# Main_IF_Board_A.net
KiCad netlist of a schematic drawn in Altium Designer
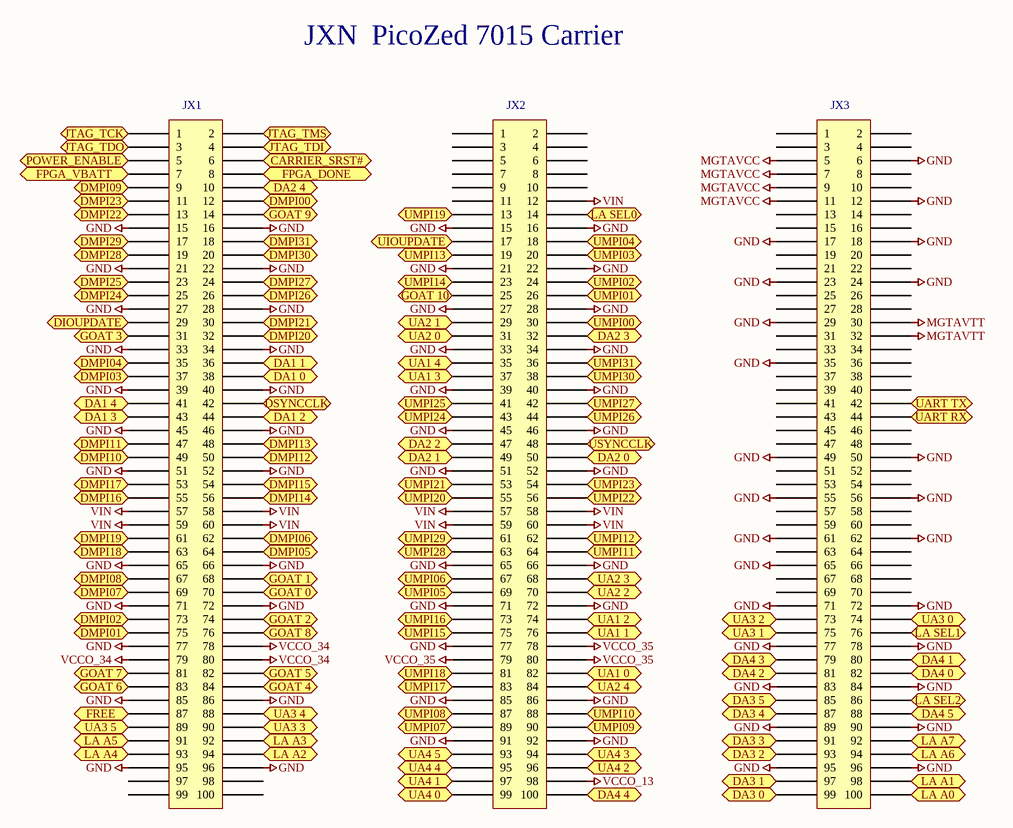
[diagram p0: Main IF Board A.SchDoc]

(export (version "E")
  (design (tool "Eeschema 10.0.6"))
  (components
    (comp (ref "JXN")
      (value "PicoZed 7015 Carrier")
      (footprint "BergStak61083")
      (libsource (lib "lib_RF_passives 1") (part "PicoZed7015 Carrier"))
    )
  )
  (nets
    (net (code "1") (name "/CARRIER_SRST#") (class "Default")
      (node (ref "JXN") (pin "106") (pinfunction "6_106") (pintype "passive"))
    )
    (net (code "2") (name "/DA1 0") (class "Default")
      (node (ref "JXN") (pin "138") (pinfunction "38_138") (pintype "passive"))
    )
    (net (code "3") (name "/DA1 1") (class "Default")
      (node (ref "JXN") (pin "136") (pinfunction "36_136") (pintype "passive"))
    )
    (net (code "4") (name "/DA1 2") (class "Default")
      (node (ref "JXN") (pin "144") (pinfunction "44_144") (pintype "passive"))
    )
    (net (code "5") (name "/DA1 3") (class "Default")
      (node (ref "JXN") (pin "143") (pinfunction "43_143") (pintype "passive"))
    )
    (net (code "6") (name "/DA1 4") (class "Default")
      (node (ref "JXN") (pin "141") (pinfunction "41_141") (pintype "passive"))
    )
    (net (code "7") (name "/DA2 0") (class "Default")
      (node (ref "JXN") (pin "250") (pinfunction "50_250") (pintype "passive"))
    )
    (net (code "8") (name "/DA2 1") (class "Default")
      (node (ref "JXN") (pin "249") (pinfunction "49_249") (pintype "passive"))
    )
    (net (code "9") (name "/DA2 2") (class "Default")
      (node (ref "JXN") (pin "247") (pinfunction "47_247") (pintype "passive"))
    )
    (net (code "10") (name "/DA2 3") (class "Default")
      (node (ref "JXN") (pin "232") (pinfunction "32_232") (pintype "passive"))
    )
    (net (code "11") (name "/DA2 4") (class "Default")
      (node (ref "JXN") (pin "110") (pinfunction "10_110") (pintype "passive"))
    )
    (net (code "12") (name "/DA3 0") (class "Default")
      (node (ref "JXN") (pin "399") (pinfunction "99_399") (pintype "passive"))
    )
    (net (code "13") (name "/DA3 1") (class "Default")
      (node (ref "JXN") (pin "397") (pinfunction "97_397") (pintype "passive"))
    )
    (net (code "14") (name "/DA3 2") (class "Default")
      (node (ref "JXN") (pin "393") (pinfunction "93_393") (pintype "passive"))
    )
    (net (code "15") (name "/DA3 3") (class "Default")
      (node (ref "JXN") (pin "391") (pinfunction "91_391") (pintype "passive"))
    )
    (net (code "16") (name "/DA3 4") (class "Default")
      (node (ref "JXN") (pin "387") (pinfunction "87_387") (pintype "passive"))
    )
    (net (code "17") (name "/DA3 5") (class "Default")
      (node (ref "JXN") (pin "385") (pinfunction "85_385") (pintype "passive"))
    )
    (net (code "18") (name "/DA4 0") (class "Default")
      (node (ref "JXN") (pin "382") (pinfunction "82_382") (pintype "passive"))
    )
    (net (code "19") (name "/DA4 1") (class "Default")
      (node (ref "JXN") (pin "380") (pinfunction "80_380") (pintype "passive"))
    )
    (net (code "20") (name "/DA4 2") (class "Default")
      (node (ref "JXN") (pin "381") (pinfunction "81_381") (pintype "passive"))
    )
    (net (code "21") (name "/DA4 3") (class "Default")
      (node (ref "JXN") (pin "379") (pinfunction "79_379") (pintype "passive"))
    )
    (net (code "22") (name "/DA4 4") (class "Default")
      (node (ref "JXN") (pin "300") (pinfunction "100_300") (pintype "passive"))
    )
    (net (code "23") (name "/DA4 5") (class "Default")
      (node (ref "JXN") (pin "388") (pinfunction "88_388") (pintype "passive"))
    )
    (net (code "24") (name "/DIOUPDATE") (class "Default")
      (node (ref "JXN") (pin "129") (pinfunction "29_129") (pintype "passive"))
    )
    (net (code "25") (name "/DMPI00") (class "Default")
      (node (ref "JXN") (pin "112") (pinfunction "12_112") (pintype "passive"))
    )
    (net (code "26") (name "/DMPI01") (class "Default")
      (node (ref "JXN") (pin "175") (pinfunction "75_175") (pintype "passive"))
    )
    (net (code "27") (name "/DMPI02") (class "Default")
      (node (ref "JXN") (pin "173") (pinfunction "73_173") (pintype "passive"))
    )
    (net (code "28") (name "/DMPI03") (class "Default")
      (node (ref "JXN") (pin "137") (pinfunction "37_137") (pintype "passive"))
    )
    (net (code "29") (name "/DMPI04") (class "Default")
      (node (ref "JXN") (pin "135") (pinfunction "35_135") (pintype "passive"))
    )
    (net (code "30") (name "/DMPI05") (class "Default")
      (node (ref "JXN") (pin "164") (pinfunction "64_164") (pintype "passive"))
    )
    (net (code "31") (name "/DMPI06") (class "Default")
      (node (ref "JXN") (pin "162") (pinfunction "62_162") (pintype "passive"))
    )
    (net (code "32") (name "/DMPI07") (class "Default")
      (node (ref "JXN") (pin "169") (pinfunction "69_169") (pintype "passive"))
    )
    (net (code "33") (name "/DMPI08") (class "Default")
      (node (ref "JXN") (pin "167") (pinfunction "67_167") (pintype "passive"))
    )
    (net (code "34") (name "/DMPI09") (class "Default")
      (node (ref "JXN") (pin "109") (pinfunction "9_109") (pintype "passive"))
    )
    (net (code "35") (name "/DMPI10") (class "Default")
      (node (ref "JXN") (pin "149") (pinfunction "49_149") (pintype "passive"))
    )
    (net (code "36") (name "/DMPI11") (class "Default")
      (node (ref "JXN") (pin "147") (pinfunction "47_147") (pintype "passive"))
    )
    (net (code "37") (name "/DMPI12") (class "Default")
      (node (ref "JXN") (pin "150") (pinfunction "50_150") (pintype "passive"))
    )
    (net (code "38") (name "/DMPI13") (class "Default")
      (node (ref "JXN") (pin "148") (pinfunction "48_148") (pintype "passive"))
    )
    (net (code "39") (name "/DMPI14") (class "Default")
      (node (ref "JXN") (pin "156") (pinfunction "56_156") (pintype "passive"))
    )
    (net (code "40") (name "/DMPI15") (class "Default")
      (node (ref "JXN") (pin "154") (pinfunction "54_154") (pintype "passive"))
    )
    (net (code "41") (name "/DMPI16") (class "Default")
      (node (ref "JXN") (pin "155") (pinfunction "55_155") (pintype "passive"))
    )
    (net (code "42") (name "/DMPI17") (class "Default")
      (node (ref "JXN") (pin "153") (pinfunction "53_153") (pintype "passive"))
    )
    (net (code "43") (name "/DMPI18") (class "Default")
      (node (ref "JXN") (pin "163") (pinfunction "63_163") (pintype "passive"))
    )
    (net (code "44") (name "/DMPI19") (class "Default")
      (node (ref "JXN") (pin "161") (pinfunction "61_161") (pintype "passive"))
    )
    (net (code "45") (name "/DMPI20") (class "Default")
      (node (ref "JXN") (pin "132") (pinfunction "32_132") (pintype "passive"))
    )
    (net (code "46") (name "/DMPI21") (class "Default")
      (node (ref "JXN") (pin "130") (pinfunction "30_130") (pintype "passive"))
    )
    (net (code "47") (name "/DMPI22") (class "Default")
      (node (ref "JXN") (pin "113") (pinfunction "13_113") (pintype "passive"))
    )
    (net (code "48") (name "/DMPI23") (class "Default")
      (node (ref "JXN") (pin "111") (pinfunction "11_111") (pintype "passive"))
    )
    (net (code "49") (name "/DMPI24") (class "Default")
      (node (ref "JXN") (pin "125") (pinfunction "25_125") (pintype "passive"))
    )
    (net (code "50") (name "/DMPI25") (class "Default")
      (node (ref "JXN") (pin "123") (pinfunction "23_123") (pintype "passive"))
    )
    (net (code "51") (name "/DMPI26") (class "Default")
      (node (ref "JXN") (pin "126") (pinfunction "26_126") (pintype "passive"))
    )
    (net (code "52") (name "/DMPI27") (class "Default")
      (node (ref "JXN") (pin "124") (pinfunction "24_124") (pintype "passive"))
    )
    (net (code "53") (name "/DMPI28") (class "Default")
      (node (ref "JXN") (pin "119") (pinfunction "19_119") (pintype "passive"))
    )
    (net (code "54") (name "/DMPI29") (class "Default")
      (node (ref "JXN") (pin "117") (pinfunction "17_117") (pintype "passive"))
    )
    (net (code "55") (name "/DMPI30") (class "Default")
      (node (ref "JXN") (pin "120") (pinfunction "20_120") (pintype "passive"))
    )
    (net (code "56") (name "/DMPI31") (class "Default")
      (node (ref "JXN") (pin "118") (pinfunction "18_118") (pintype "passive"))
    )
    (net (code "57") (name "/DSYNCCLK") (class "Default")
      (node (ref "JXN") (pin "142") (pinfunction "42_142") (pintype "passive"))
    )
    (net (code "58") (name "/FPGA_DONE") (class "Default")
      (node (ref "JXN") (pin "108") (pinfunction "8_108") (pintype "passive"))
    )
    (net (code "59") (name "/FPGA_VBATT") (class "Default")
      (node (ref "JXN") (pin "107") (pinfunction "7_107") (pintype "passive"))
    )
    (net (code "60") (name "/FREE") (class "Default")
      (node (ref "JXN") (pin "187") (pinfunction "87_187") (pintype "passive"))
    )
    (net (code "61") (name "/GOAT 0") (class "Default")
      (node (ref "JXN") (pin "170") (pinfunction "70_170") (pintype "passive"))
    )
    (net (code "62") (name "/GOAT 1") (class "Default")
      (node (ref "JXN") (pin "168") (pinfunction "68_168") (pintype "passive"))
    )
    (net (code "63") (name "/GOAT 2") (class "Default")
      (node (ref "JXN") (pin "174") (pinfunction "74_174") (pintype "passive"))
    )
    (net (code "64") (name "/GOAT 3") (class "Default")
      (node (ref "JXN") (pin "131") (pinfunction "31_131") (pintype "passive"))
    )
    (net (code "65") (name "/GOAT 4") (class "Default")
      (node (ref "JXN") (pin "184") (pinfunction "84_184") (pintype "passive"))
    )
    (net (code "66") (name "/GOAT 5") (class "Default")
      (node (ref "JXN") (pin "182") (pinfunction "82_182") (pintype "passive"))
    )
    (net (code "67") (name "/GOAT 6") (class "Default")
      (node (ref "JXN") (pin "183") (pinfunction "83_183") (pintype "passive"))
    )
    (net (code "68") (name "/GOAT 7") (class "Default")
      (node (ref "JXN") (pin "181") (pinfunction "81_181") (pintype "passive"))
    )
    (net (code "69") (name "/GOAT 8") (class "Default")
      (node (ref "JXN") (pin "176") (pinfunction "76_176") (pintype "passive"))
    )
    (net (code "70") (name "/GOAT 9") (class "Default")
      (node (ref "JXN") (pin "114") (pinfunction "14_114") (pintype "passive"))
    )
    (net (code "71") (name "/GOAT 10") (class "Default")
      (node (ref "JXN") (pin "225") (pinfunction "25_225") (pintype "passive"))
    )
    (net (code "72") (name "/JTAG_TCK") (class "Default")
      (node (ref "JXN") (pin "101") (pinfunction "1_101") (pintype "passive"))
    )
    (net (code "73") (name "/JTAG_TDI") (class "Default")
      (node (ref "JXN") (pin "104") (pinfunction "4_104") (pintype "passive"))
    )
    (net (code "74") (name "/JTAG_TDO") (class "Default")
      (node (ref "JXN") (pin "103") (pinfunction "3_103") (pintype "passive"))
    )
    (net (code "75") (name "/JTAG_TMS") (class "Default")
      (node (ref "JXN") (pin "102") (pinfunction "2_102") (pintype "passive"))
    )
    (net (code "76") (name "/LA A0") (class "Default")
      (node (ref "JXN") (pin "400") (pinfunction "100_400") (pintype "passive"))
    )
    (net (code "77") (name "/LA A1") (class "Default")
      (node (ref "JXN") (pin "398") (pinfunction "98_398") (pintype "passive"))
    )
    (net (code "78") (name "/LA A2") (class "Default")
      (node (ref "JXN") (pin "194") (pinfunction "94_194") (pintype "passive"))
    )
    (net (code "79") (name "/LA A3") (class "Default")
      (node (ref "JXN") (pin "192") (pinfunction "92_192") (pintype "passive"))
    )
    (net (code "80") (name "/LA A4") (class "Default")
      (node (ref "JXN") (pin "193") (pinfunction "93_193") (pintype "passive"))
    )
    (net (code "81") (name "/LA A5") (class "Default")
      (node (ref "JXN") (pin "191") (pinfunction "91_191") (pintype "passive"))
    )
    (net (code "82") (name "/LA A6") (class "Default")
      (node (ref "JXN") (pin "394") (pinfunction "94_394") (pintype "passive"))
    )
    (net (code "83") (name "/LA A7") (class "Default")
      (node (ref "JXN") (pin "392") (pinfunction "92_392") (pintype "passive"))
    )
    (net (code "84") (name "/LA SEL0") (class "Default")
      (node (ref "JXN") (pin "214") (pinfunction "14_214") (pintype "passive"))
    )
    (net (code "85") (name "/LA SEL1") (class "Default")
      (node (ref "JXN") (pin "376") (pinfunction "76_376") (pintype "passive"))
    )
    (net (code "86") (name "/LA SEL2") (class "Default")
      (node (ref "JXN") (pin "386") (pinfunction "86_386") (pintype "passive"))
    )
    (net (code "87") (name "/POWER_ENABLE") (class "Default")
      (node (ref "JXN") (pin "105") (pinfunction "5_105") (pintype "passive"))
    )
    (net (code "88") (name "/UA1 0") (class "Default")
      (node (ref "JXN") (pin "282") (pinfunction "82_282") (pintype "passive"))
    )
    (net (code "89") (name "/UA1 1") (class "Default")
      (node (ref "JXN") (pin "276") (pinfunction "76_276") (pintype "passive"))
    )
    (net (code "90") (name "/UA1 2") (class "Default")
      (node (ref "JXN") (pin "274") (pinfunction "74_274") (pintype "passive"))
    )
    (net (code "91") (name "/UA1 3") (class "Default")
      (node (ref "JXN") (pin "237") (pinfunction "37_237") (pintype "passive"))
    )
    (net (code "92") (name "/UA1 4") (class "Default")
      (node (ref "JXN") (pin "235") (pinfunction "35_235") (pintype "passive"))
    )
    (net (code "93") (name "/UA2 0") (class "Default")
      (node (ref "JXN") (pin "231") (pinfunction "31_231") (pintype "passive"))
    )
    (net (code "94") (name "/UA2 1") (class "Default")
      (node (ref "JXN") (pin "229") (pinfunction "29_229") (pintype "passive"))
    )
    (net (code "95") (name "/UA2 2") (class "Default")
      (node (ref "JXN") (pin "270") (pinfunction "70_270") (pintype "passive"))
    )
    (net (code "96") (name "/UA2 3") (class "Default")
      (node (ref "JXN") (pin "268") (pinfunction "68_268") (pintype "passive"))
    )
    (net (code "97") (name "/UA2 4") (class "Default")
      (node (ref "JXN") (pin "284") (pinfunction "84_284") (pintype "passive"))
    )
    (net (code "98") (name "/UA3 0") (class "Default")
      (node (ref "JXN") (pin "374") (pinfunction "74_374") (pintype "passive"))
    )
    (net (code "99") (name "/UA3 1") (class "Default")
      (node (ref "JXN") (pin "375") (pinfunction "75_375") (pintype "passive"))
    )
    (net (code "100") (name "/UA3 2") (class "Default")
      (node (ref "JXN") (pin "373") (pinfunction "73_373") (pintype "passive"))
    )
    (net (code "101") (name "/UA3 3") (class "Default")
      (node (ref "JXN") (pin "190") (pinfunction "90_190") (pintype "passive"))
    )
    (net (code "102") (name "/UA3 4") (class "Default")
      (node (ref "JXN") (pin "188") (pinfunction "88_188") (pintype "passive"))
    )
    (net (code "103") (name "/UA3 5") (class "Default")
      (node (ref "JXN") (pin "189") (pinfunction "89_189") (pintype "passive"))
    )
    (net (code "104") (name "/UA4 0") (class "Default")
      (node (ref "JXN") (pin "299") (pinfunction "99_299") (pintype "passive"))
    )
    (net (code "105") (name "/UA4 1") (class "Default")
      (node (ref "JXN") (pin "297") (pinfunction "97_297") (pintype "passive"))
    )
    (net (code "106") (name "/UA4 2") (class "Default")
      (node (ref "JXN") (pin "296") (pinfunction "96_296") (pintype "passive"))
    )
    (net (code "107") (name "/UA4 3") (class "Default")
      (node (ref "JXN") (pin "294") (pinfunction "94_294") (pintype "passive"))
    )
    (net (code "108") (name "/UA4 4") (class "Default")
      (node (ref "JXN") (pin "295") (pinfunction "95_295") (pintype "passive"))
    )
    (net (code "109") (name "/UA4 5") (class "Default")
      (node (ref "JXN") (pin "293") (pinfunction "93_293") (pintype "passive"))
    )
    (net (code "110") (name "/UART RX") (class "Default")
      (node (ref "JXN") (pin "344") (pinfunction "44_344") (pintype "passive"))
    )
    (net (code "111") (name "/UART TX") (class "Default")
      (node (ref "JXN") (pin "342") (pinfunction "42_342") (pintype "passive"))
    )
    (net (code "112") (name "/UIOUPDATE") (class "Default")
      (node (ref "JXN") (pin "217") (pinfunction "17_217") (pintype "passive"))
    )
    (net (code "113") (name "/UMPI00") (class "Default")
      (node (ref "JXN") (pin "230") (pinfunction "30_230") (pintype "passive"))
    )
    (net (code "114") (name "/UMPI01") (class "Default")
      (node (ref "JXN") (pin "226") (pinfunction "26_226") (pintype "passive"))
    )
    (net (code "115") (name "/UMPI02") (class "Default")
      (node (ref "JXN") (pin "224") (pinfunction "24_224") (pintype "passive"))
    )
    (net (code "116") (name "/UMPI03") (class "Default")
      (node (ref "JXN") (pin "220") (pinfunction "20_220") (pintype "passive"))
    )
    (net (code "117") (name "/UMPI04") (class "Default")
      (node (ref "JXN") (pin "218") (pinfunction "18_218") (pintype "passive"))
    )
    (net (code "118") (name "/UMPI05") (class "Default")
      (node (ref "JXN") (pin "269") (pinfunction "69_269") (pintype "passive"))
    )
    (net (code "119") (name "/UMPI06") (class "Default")
      (node (ref "JXN") (pin "267") (pinfunction "67_267") (pintype "passive"))
    )
    (net (code "120") (name "/UMPI07") (class "Default")
      (node (ref "JXN") (pin "289") (pinfunction "89_289") (pintype "passive"))
    )
    (net (code "121") (name "/UMPI08") (class "Default")
      (node (ref "JXN") (pin "287") (pinfunction "87_287") (pintype "passive"))
    )
    (net (code "122") (name "/UMPI09") (class "Default")
      (node (ref "JXN") (pin "290") (pinfunction "90_290") (pintype "passive"))
    )
    (net (code "123") (name "/UMPI10") (class "Default")
      (node (ref "JXN") (pin "288") (pinfunction "88_288") (pintype "passive"))
    )
    (net (code "124") (name "/UMPI11") (class "Default")
      (node (ref "JXN") (pin "264") (pinfunction "64_264") (pintype "passive"))
    )
    (net (code "125") (name "/UMPI12") (class "Default")
      (node (ref "JXN") (pin "262") (pinfunction "62_262") (pintype "passive"))
    )
    (net (code "126") (name "/UMPI13") (class "Default")
      (node (ref "JXN") (pin "219") (pinfunction "19_219") (pintype "passive"))
    )
    (net (code "127") (name "/UMPI14") (class "Default")
      (node (ref "JXN") (pin "223") (pinfunction "23_223") (pintype "passive"))
    )
    (net (code "128") (name "/UMPI15") (class "Default")
      (node (ref "JXN") (pin "275") (pinfunction "75_275") (pintype "passive"))
    )
    (net (code "129") (name "/UMPI16") (class "Default")
      (node (ref "JXN") (pin "273") (pinfunction "73_273") (pintype "passive"))
    )
    (net (code "130") (name "/UMPI17") (class "Default")
      (node (ref "JXN") (pin "283") (pinfunction "83_283") (pintype "passive"))
    )
    (net (code "131") (name "/UMPI18") (class "Default")
      (node (ref "JXN") (pin "281") (pinfunction "81_281") (pintype "passive"))
    )
    (net (code "132") (name "/UMPI19") (class "Default")
      (node (ref "JXN") (pin "213") (pinfunction "13_213") (pintype "passive"))
    )
    (net (code "133") (name "/UMPI20") (class "Default")
      (node (ref "JXN") (pin "255") (pinfunction "55_255") (pintype "passive"))
    )
    (net (code "134") (name "/UMPI21") (class "Default")
      (node (ref "JXN") (pin "253") (pinfunction "53_253") (pintype "passive"))
    )
    (net (code "135") (name "/UMPI22") (class "Default")
      (node (ref "JXN") (pin "256") (pinfunction "56_256") (pintype "passive"))
    )
    (net (code "136") (name "/UMPI23") (class "Default")
      (node (ref "JXN") (pin "254") (pinfunction "54_254") (pintype "passive"))
    )
    (net (code "137") (name "/UMPI24") (class "Default")
      (node (ref "JXN") (pin "243") (pinfunction "43_243") (pintype "passive"))
    )
    (net (code "138") (name "/UMPI25") (class "Default")
      (node (ref "JXN") (pin "241") (pinfunction "41_241") (pintype "passive"))
    )
    (net (code "139") (name "/UMPI26") (class "Default")
      (node (ref "JXN") (pin "244") (pinfunction "44_244") (pintype "passive"))
    )
    (net (code "140") (name "/UMPI27") (class "Default")
      (node (ref "JXN") (pin "242") (pinfunction "42_242") (pintype "passive"))
    )
    (net (code "141") (name "/UMPI28") (class "Default")
      (node (ref "JXN") (pin "263") (pinfunction "63_263") (pintype "passive"))
    )
    (net (code "142") (name "/UMPI29") (class "Default")
      (node (ref "JXN") (pin "261") (pinfunction "61_261") (pintype "passive"))
    )
    (net (code "143") (name "/UMPI30") (class "Default")
      (node (ref "JXN") (pin "238") (pinfunction "38_238") (pintype "passive"))
    )
    (net (code "144") (name "/UMPI31") (class "Default")
      (node (ref "JXN") (pin "236") (pinfunction "36_236") (pintype "passive"))
    )
    (net (code "145") (name "/USYNCCLK") (class "Default")
      (node (ref "JXN") (pin "248") (pinfunction "48_248") (pintype "passive"))
    )
    (net (code "146") (name "GND") (class "Default")
      (node (ref "JXN") (pin "115") (pinfunction "15_115") (pintype "passive"))
      (node (ref "JXN") (pin "116") (pinfunction "16_116") (pintype "passive"))
      (node (ref "JXN") (pin "121") (pinfunction "21_121") (pintype "passive"))
      (node (ref "JXN") (pin "122") (pinfunction "22_122") (pintype "passive"))
      (node (ref "JXN") (pin "127") (pinfunction "27_127") (pintype "passive"))
      (node (ref "JXN") (pin "128") (pinfunction "28_128") (pintype "passive"))
      (node (ref "JXN") (pin "133") (pinfunction "33_133") (pintype "passive"))
      (node (ref "JXN") (pin "134") (pinfunction "34_134") (pintype "passive"))
      (node (ref "JXN") (pin "139") (pinfunction "39_139") (pintype "passive"))
      (node (ref "JXN") (pin "140") (pinfunction "40_140") (pintype "passive"))
      (node (ref "JXN") (pin "145") (pinfunction "45_145") (pintype "passive"))
      (node (ref "JXN") (pin "146") (pinfunction "46_146") (pintype "passive"))
      (node (ref "JXN") (pin "151") (pinfunction "51_151") (pintype "passive"))
      (node (ref "JXN") (pin "152") (pinfunction "52_152") (pintype "passive"))
      (node (ref "JXN") (pin "165") (pinfunction "65_165") (pintype "passive"))
      (node (ref "JXN") (pin "166") (pinfunction "66_166") (pintype "passive"))
      (node (ref "JXN") (pin "171") (pinfunction "71_171") (pintype "passive"))
      (node (ref "JXN") (pin "172") (pinfunction "72_172") (pintype "passive"))
      (node (ref "JXN") (pin "177") (pinfunction "77_177") (pintype "passive"))
      (node (ref "JXN") (pin "185") (pinfunction "85_185") (pintype "passive"))
      (node (ref "JXN") (pin "186") (pinfunction "86_186") (pintype "passive"))
      (node (ref "JXN") (pin "195") (pinfunction "95_195") (pintype "passive"))
      (node (ref "JXN") (pin "196") (pinfunction "96_196") (pintype "passive"))
      (node (ref "JXN") (pin "215") (pinfunction "15_215") (pintype "passive"))
      (node (ref "JXN") (pin "216") (pinfunction "16_216") (pintype "passive"))
      (node (ref "JXN") (pin "221") (pinfunction "21_221") (pintype "passive"))
      (node (ref "JXN") (pin "222") (pinfunction "22_222") (pintype "passive"))
      (node (ref "JXN") (pin "227") (pinfunction "27_227") (pintype "passive"))
      (node (ref "JXN") (pin "228") (pinfunction "28_228") (pintype "passive"))
      (node (ref "JXN") (pin "233") (pinfunction "33_233") (pintype "passive"))
      (node (ref "JXN") (pin "234") (pinfunction "34_234") (pintype "passive"))
      (node (ref "JXN") (pin "239") (pinfunction "39_239") (pintype "passive"))
      (node (ref "JXN") (pin "240") (pinfunction "40_240") (pintype "passive"))
      (node (ref "JXN") (pin "245") (pinfunction "45_245") (pintype "passive"))
      (node (ref "JXN") (pin "246") (pinfunction "46_246") (pintype "passive"))
      (node (ref "JXN") (pin "251") (pinfunction "51_251") (pintype "passive"))
      (node (ref "JXN") (pin "252") (pinfunction "52_252") (pintype "passive"))
      (node (ref "JXN") (pin "265") (pinfunction "65_265") (pintype "passive"))
      (node (ref "JXN") (pin "266") (pinfunction "66_266") (pintype "passive"))
      (node (ref "JXN") (pin "271") (pinfunction "71_271") (pintype "passive"))
      (node (ref "JXN") (pin "272") (pinfunction "72_272") (pintype "passive"))
      (node (ref "JXN") (pin "277") (pinfunction "77_277") (pintype "passive"))
      (node (ref "JXN") (pin "285") (pinfunction "85_285") (pintype "passive"))
      (node (ref "JXN") (pin "286") (pinfunction "86_286") (pintype "passive"))
      (node (ref "JXN") (pin "291") (pinfunction "91_291") (pintype "passive"))
      (node (ref "JXN") (pin "292") (pinfunction "92_292") (pintype "passive"))
      (node (ref "JXN") (pin "306") (pinfunction "6_306") (pintype "passive"))
      (node (ref "JXN") (pin "312") (pinfunction "12_312") (pintype "passive"))
      (node (ref "JXN") (pin "317") (pinfunction "17_317") (pintype "passive"))
      (node (ref "JXN") (pin "318") (pinfunction "18_318") (pintype "passive"))
      (node (ref "JXN") (pin "323") (pinfunction "23_323") (pintype "passive"))
      (node (ref "JXN") (pin "324") (pinfunction "24_324") (pintype "passive"))
      (node (ref "JXN") (pin "329") (pinfunction "29_329") (pintype "passive"))
      (node (ref "JXN") (pin "335") (pinfunction "35_335") (pintype "passive"))
      (node (ref "JXN") (pin "349") (pinfunction "49_349") (pintype "passive"))
      (node (ref "JXN") (pin "350") (pinfunction "50_350") (pintype "passive"))
      (node (ref "JXN") (pin "355") (pinfunction "55_355") (pintype "passive"))
      (node (ref "JXN") (pin "356") (pinfunction "56_356") (pintype "passive"))
      (node (ref "JXN") (pin "361") (pinfunction "61_361") (pintype "passive"))
      (node (ref "JXN") (pin "362") (pinfunction "62_362") (pintype "passive"))
      (node (ref "JXN") (pin "365") (pinfunction "65_365") (pintype "passive"))
      (node (ref "JXN") (pin "371") (pinfunction "71_371") (pintype "passive"))
      (node (ref "JXN") (pin "372") (pinfunction "72_372") (pintype "passive"))
      (node (ref "JXN") (pin "377") (pinfunction "77_377") (pintype "passive"))
      (node (ref "JXN") (pin "378") (pinfunction "78_378") (pintype "passive"))
      (node (ref "JXN") (pin "383") (pinfunction "83_383") (pintype "passive"))
      (node (ref "JXN") (pin "384") (pinfunction "84_384") (pintype "passive"))
      (node (ref "JXN") (pin "389") (pinfunction "89_389") (pintype "passive"))
      (node (ref "JXN") (pin "390") (pinfunction "90_390") (pintype "passive"))
      (node (ref "JXN") (pin "395") (pinfunction "95_395") (pintype "passive"))
      (node (ref "JXN") (pin "396") (pinfunction "96_396") (pintype "passive"))
    )
    (net (code "147") (name "MGTAVCC") (class "Default")
      (node (ref "JXN") (pin "305") (pinfunction "5_305") (pintype "passive"))
      (node (ref "JXN") (pin "307") (pinfunction "7_307") (pintype "passive"))
      (node (ref "JXN") (pin "309") (pinfunction "9_309") (pintype "passive"))
      (node (ref "JXN") (pin "311") (pinfunction "11_311") (pintype "passive"))
    )
    (net (code "148") (name "MGTAVTT") (class "Default")
      (node (ref "JXN") (pin "330") (pinfunction "30_330") (pintype "passive"))
      (node (ref "JXN") (pin "332") (pinfunction "32_332") (pintype "passive"))
    )
    (net (code "149") (name "VCCO_13") (class "Default")
      (node (ref "JXN") (pin "298") (pinfunction "98_298") (pintype "passive"))
    )
    (net (code "150") (name "VCCO_34") (class "Default")
      (node (ref "JXN") (pin "178") (pinfunction "78_178") (pintype "passive"))
      (node (ref "JXN") (pin "179") (pinfunction "79_179") (pintype "passive"))
      (node (ref "JXN") (pin "180") (pinfunction "80_180") (pintype "passive"))
    )
    (net (code "151") (name "VCCO_35") (class "Default")
      (node (ref "JXN") (pin "278") (pinfunction "78_278") (pintype "passive"))
      (node (ref "JXN") (pin "279") (pinfunction "79_279") (pintype "passive"))
      (node (ref "JXN") (pin "280") (pinfunction "80_280") (pintype "passive"))
    )
    (net (code "152") (name "VIN") (class "Default")
      (node (ref "JXN") (pin "157") (pinfunction "57_157") (pintype "passive"))
      (node (ref "JXN") (pin "158") (pinfunction "58_158") (pintype "passive"))
      (node (ref "JXN") (pin "159") (pinfunction "59_159") (pintype "passive"))
      (node (ref "JXN") (pin "160") (pinfunction "60_160") (pintype "passive"))
      (node (ref "JXN") (pin "212") (pinfunction "12_212") (pintype "passive"))
      (node (ref "JXN") (pin "257") (pinfunction "57_257") (pintype "passive"))
      (node (ref "JXN") (pin "258") (pinfunction "58_258") (pintype "passive"))
      (node (ref "JXN") (pin "259") (pinfunction "59_259") (pintype "passive"))
      (node (ref "JXN") (pin "260") (pinfunction "60_260") (pintype "passive"))
    )
    (net (code "153") (name "unconnected-(JXN-1-Pad201)") (class "Default")
      (node (ref "JXN") (pin "201") (pinfunction "1_201") (pintype "passive"))
    )
    (net (code "154") (name "unconnected-(JXN-1-Pad301)") (class "Default")
      (node (ref "JXN") (pin "301") (pinfunction "1_301") (pintype "passive"))
    )
    (net (code "155") (name "unconnected-(JXN-2-Pad202)") (class "Default")
      (node (ref "JXN") (pin "202") (pinfunction "2_202") (pintype "passive"))
    )
    (net (code "156") (name "unconnected-(JXN-2-Pad302)") (class "Default")
      (node (ref "JXN") (pin "302") (pinfunction "2_302") (pintype "passive"))
    )
    (net (code "157") (name "unconnected-(JXN-3-Pad203)") (class "Default")
      (node (ref "JXN") (pin "203") (pinfunction "3_203") (pintype "passive"))
    )
    (net (code "158") (name "unconnected-(JXN-3-Pad303)") (class "Default")
      (node (ref "JXN") (pin "303") (pinfunction "3_303") (pintype "passive"))
    )
    (net (code "159") (name "unconnected-(JXN-4-Pad204)") (class "Default")
      (node (ref "JXN") (pin "204") (pinfunction "4_204") (pintype "passive"))
    )
    (net (code "160") (name "unconnected-(JXN-4-Pad304)") (class "Default")
      (node (ref "JXN") (pin "304") (pinfunction "4_304") (pintype "passive"))
    )
    (net (code "161") (name "unconnected-(JXN-5-Pad205)") (class "Default")
      (node (ref "JXN") (pin "205") (pinfunction "5_205") (pintype "passive"))
    )
    (net (code "162") (name "unconnected-(JXN-6-Pad206)") (class "Default")
      (node (ref "JXN") (pin "206") (pinfunction "6_206") (pintype "passive"))
    )
    (net (code "163") (name "unconnected-(JXN-7-Pad207)") (class "Default")
      (node (ref "JXN") (pin "207") (pinfunction "7_207") (pintype "passive"))
    )
    (net (code "164") (name "unconnected-(JXN-8-Pad208)") (class "Default")
      (node (ref "JXN") (pin "208") (pinfunction "8_208") (pintype "passive"))
    )
    (net (code "165") (name "unconnected-(JXN-8-Pad308)") (class "Default")
      (node (ref "JXN") (pin "308") (pinfunction "8_308") (pintype "passive"))
    )
    (net (code "166") (name "unconnected-(JXN-9-Pad209)") (class "Default")
      (node (ref "JXN") (pin "209") (pinfunction "9_209") (pintype "passive"))
    )
    (net (code "167") (name "unconnected-(JXN-10-Pad210)") (class "Default")
      (node (ref "JXN") (pin "210") (pinfunction "10_210") (pintype "passive"))
    )
    (net (code "168") (name "unconnected-(JXN-10-Pad310)") (class "Default")
      (node (ref "JXN") (pin "310") (pinfunction "10_310") (pintype "passive"))
    )
    (net (code "169") (name "unconnected-(JXN-11-Pad211)") (class "Default")
      (node (ref "JXN") (pin "211") (pinfunction "11_211") (pintype "passive"))
    )
    (net (code "170") (name "unconnected-(JXN-13-Pad313)") (class "Default")
      (node (ref "JXN") (pin "313") (pinfunction "13_313") (pintype "passive"))
    )
    (net (code "171") (name "unconnected-(JXN-14-Pad314)") (class "Default")
      (node (ref "JXN") (pin "314") (pinfunction "14_314") (pintype "passive"))
    )
    (net (code "172") (name "unconnected-(JXN-15-Pad315)") (class "Default")
      (node (ref "JXN") (pin "315") (pinfunction "15_315") (pintype "passive"))
    )
    (net (code "173") (name "unconnected-(JXN-16-Pad316)") (class "Default")
      (node (ref "JXN") (pin "316") (pinfunction "16_316") (pintype "passive"))
    )
    (net (code "174") (name "unconnected-(JXN-19-Pad319)") (class "Default")
      (node (ref "JXN") (pin "319") (pinfunction "19_319") (pintype "passive"))
    )
    (net (code "175") (name "unconnected-(JXN-20-Pad320)") (class "Default")
      (node (ref "JXN") (pin "320") (pinfunction "20_320") (pintype "passive"))
    )
    (net (code "176") (name "unconnected-(JXN-21-Pad321)") (class "Default")
      (node (ref "JXN") (pin "321") (pinfunction "21_321") (pintype "passive"))
    )
    (net (code "177") (name "unconnected-(JXN-22-Pad322)") (class "Default")
      (node (ref "JXN") (pin "322") (pinfunction "22_322") (pintype "passive"))
    )
    (net (code "178") (name "unconnected-(JXN-25-Pad325)") (class "Default")
      (node (ref "JXN") (pin "325") (pinfunction "25_325") (pintype "passive"))
    )
    (net (code "179") (name "unconnected-(JXN-26-Pad326)") (class "Default")
      (node (ref "JXN") (pin "326") (pinfunction "26_326") (pintype "passive"))
    )
    (net (code "180") (name "unconnected-(JXN-27-Pad327)") (class "Default")
      (node (ref "JXN") (pin "327") (pinfunction "27_327") (pintype "passive"))
    )
    (net (code "181") (name "unconnected-(JXN-28-Pad328)") (class "Default")
      (node (ref "JXN") (pin "328") (pinfunction "28_328") (pintype "passive"))
    )
    (net (code "182") (name "unconnected-(JXN-31-Pad331)") (class "Default")
      (node (ref "JXN") (pin "331") (pinfunction "31_331") (pintype "passive"))
    )
    (net (code "183") (name "unconnected-(JXN-33-Pad333)") (class "Default")
      (node (ref "JXN") (pin "333") (pinfunction "33_333") (pintype "passive"))
    )
    (net (code "184") (name "unconnected-(JXN-34-Pad334)") (class "Default")
      (node (ref "JXN") (pin "334") (pinfunction "34_334") (pintype "passive"))
    )
    (net (code "185") (name "unconnected-(JXN-36-Pad336)") (class "Default")
      (node (ref "JXN") (pin "336") (pinfunction "36_336") (pintype "passive"))
    )
    (net (code "186") (name "unconnected-(JXN-37-Pad337)") (class "Default")
      (node (ref "JXN") (pin "337") (pinfunction "37_337") (pintype "passive"))
    )
    (net (code "187") (name "unconnected-(JXN-38-Pad338)") (class "Default")
      (node (ref "JXN") (pin "338") (pinfunction "38_338") (pintype "passive"))
    )
    (net (code "188") (name "unconnected-(JXN-39-Pad339)") (class "Default")
      (node (ref "JXN") (pin "339") (pinfunction "39_339") (pintype "passive"))
    )
    (net (code "189") (name "unconnected-(JXN-40-Pad340)") (class "Default")
      (node (ref "JXN") (pin "340") (pinfunction "40_340") (pintype "passive"))
    )
    (net (code "190") (name "unconnected-(JXN-41-Pad341)") (class "Default")
      (node (ref "JXN") (pin "341") (pinfunction "41_341") (pintype "passive"))
    )
    (net (code "191") (name "unconnected-(JXN-43-Pad343)") (class "Default")
      (node (ref "JXN") (pin "343") (pinfunction "43_343") (pintype "passive"))
    )
    (net (code "192") (name "unconnected-(JXN-45-Pad345)") (class "Default")
      (node (ref "JXN") (pin "345") (pinfunction "45_345") (pintype "passive"))
    )
    (net (code "193") (name "unconnected-(JXN-46-Pad346)") (class "Default")
      (node (ref "JXN") (pin "346") (pinfunction "46_346") (pintype "passive"))
    )
    (net (code "194") (name "unconnected-(JXN-47-Pad347)") (class "Default")
      (node (ref "JXN") (pin "347") (pinfunction "47_347") (pintype "passive"))
    )
    (net (code "195") (name "unconnected-(JXN-48-Pad348)") (class "Default")
      (node (ref "JXN") (pin "348") (pinfunction "48_348") (pintype "passive"))
    )
    (net (code "196") (name "unconnected-(JXN-51-Pad351)") (class "Default")
      (node (ref "JXN") (pin "351") (pinfunction "51_351") (pintype "passive"))
    )
    (net (code "197") (name "unconnected-(JXN-52-Pad352)") (class "Default")
      (node (ref "JXN") (pin "352") (pinfunction "52_352") (pintype "passive"))
    )
    (net (code "198") (name "unconnected-(JXN-53-Pad353)") (class "Default")
      (node (ref "JXN") (pin "353") (pinfunction "53_353") (pintype "passive"))
    )
    (net (code "199") (name "unconnected-(JXN-54-Pad354)") (class "Default")
      (node (ref "JXN") (pin "354") (pinfunction "54_354") (pintype "passive"))
    )
    (net (code "200") (name "unconnected-(JXN-57-Pad357)") (class "Default")
      (node (ref "JXN") (pin "357") (pinfunction "57_357") (pintype "passive"))
    )
    (net (code "201") (name "unconnected-(JXN-58-Pad358)") (class "Default")
      (node (ref "JXN") (pin "358") (pinfunction "58_358") (pintype "passive"))
    )
    (net (code "202") (name "unconnected-(JXN-59-Pad359)") (class "Default")
      (node (ref "JXN") (pin "359") (pinfunction "59_359") (pintype "passive"))
    )
    (net (code "203") (name "unconnected-(JXN-60-Pad360)") (class "Default")
      (node (ref "JXN") (pin "360") (pinfunction "60_360") (pintype "passive"))
    )
    (net (code "204") (name "unconnected-(JXN-63-Pad363)") (class "Default")
      (node (ref "JXN") (pin "363") (pinfunction "63_363") (pintype "passive"))
    )
    (net (code "205") (name "unconnected-(JXN-64-Pad364)") (class "Default")
      (node (ref "JXN") (pin "364") (pinfunction "64_364") (pintype "passive"))
    )
    (net (code "206") (name "unconnected-(JXN-66-Pad366)") (class "Default")
      (node (ref "JXN") (pin "366") (pinfunction "66_366") (pintype "passive"))
    )
    (net (code "207") (name "unconnected-(JXN-67-Pad367)") (class "Default")
      (node (ref "JXN") (pin "367") (pinfunction "67_367") (pintype "passive"))
    )
    (net (code "208") (name "unconnected-(JXN-68-Pad368)") (class "Default")
      (node (ref "JXN") (pin "368") (pinfunction "68_368") (pintype "passive"))
    )
    (net (code "209") (name "unconnected-(JXN-69-Pad369)") (class "Default")
      (node (ref "JXN") (pin "369") (pinfunction "69_369") (pintype "passive"))
    )
    (net (code "210") (name "unconnected-(JXN-70-Pad370)") (class "Default")
      (node (ref "JXN") (pin "370") (pinfunction "70_370") (pintype "passive"))
    )
    (net (code "211") (name "unconnected-(JXN-97-Pad197)") (class "Default")
      (node (ref "JXN") (pin "197") (pinfunction "97_197") (pintype "passive"))
    )
    (net (code "212") (name "unconnected-(JXN-98-Pad198)") (class "Default")
      (node (ref "JXN") (pin "198") (pinfunction "98_198") (pintype "passive"))
    )
    (net (code "213") (name "unconnected-(JXN-99-Pad199)") (class "Default")
      (node (ref "JXN") (pin "199") (pinfunction "99_199") (pintype "passive"))
    )
    (net (code "214") (name "unconnected-(JXN-100-Pad200)") (class "Default")
      (node (ref "JXN") (pin "200") (pinfunction "100_200") (pintype "passive"))
    )
  )
)
